# ultrasound.net
KiCad netlist of a schematic drawn in EAGLE
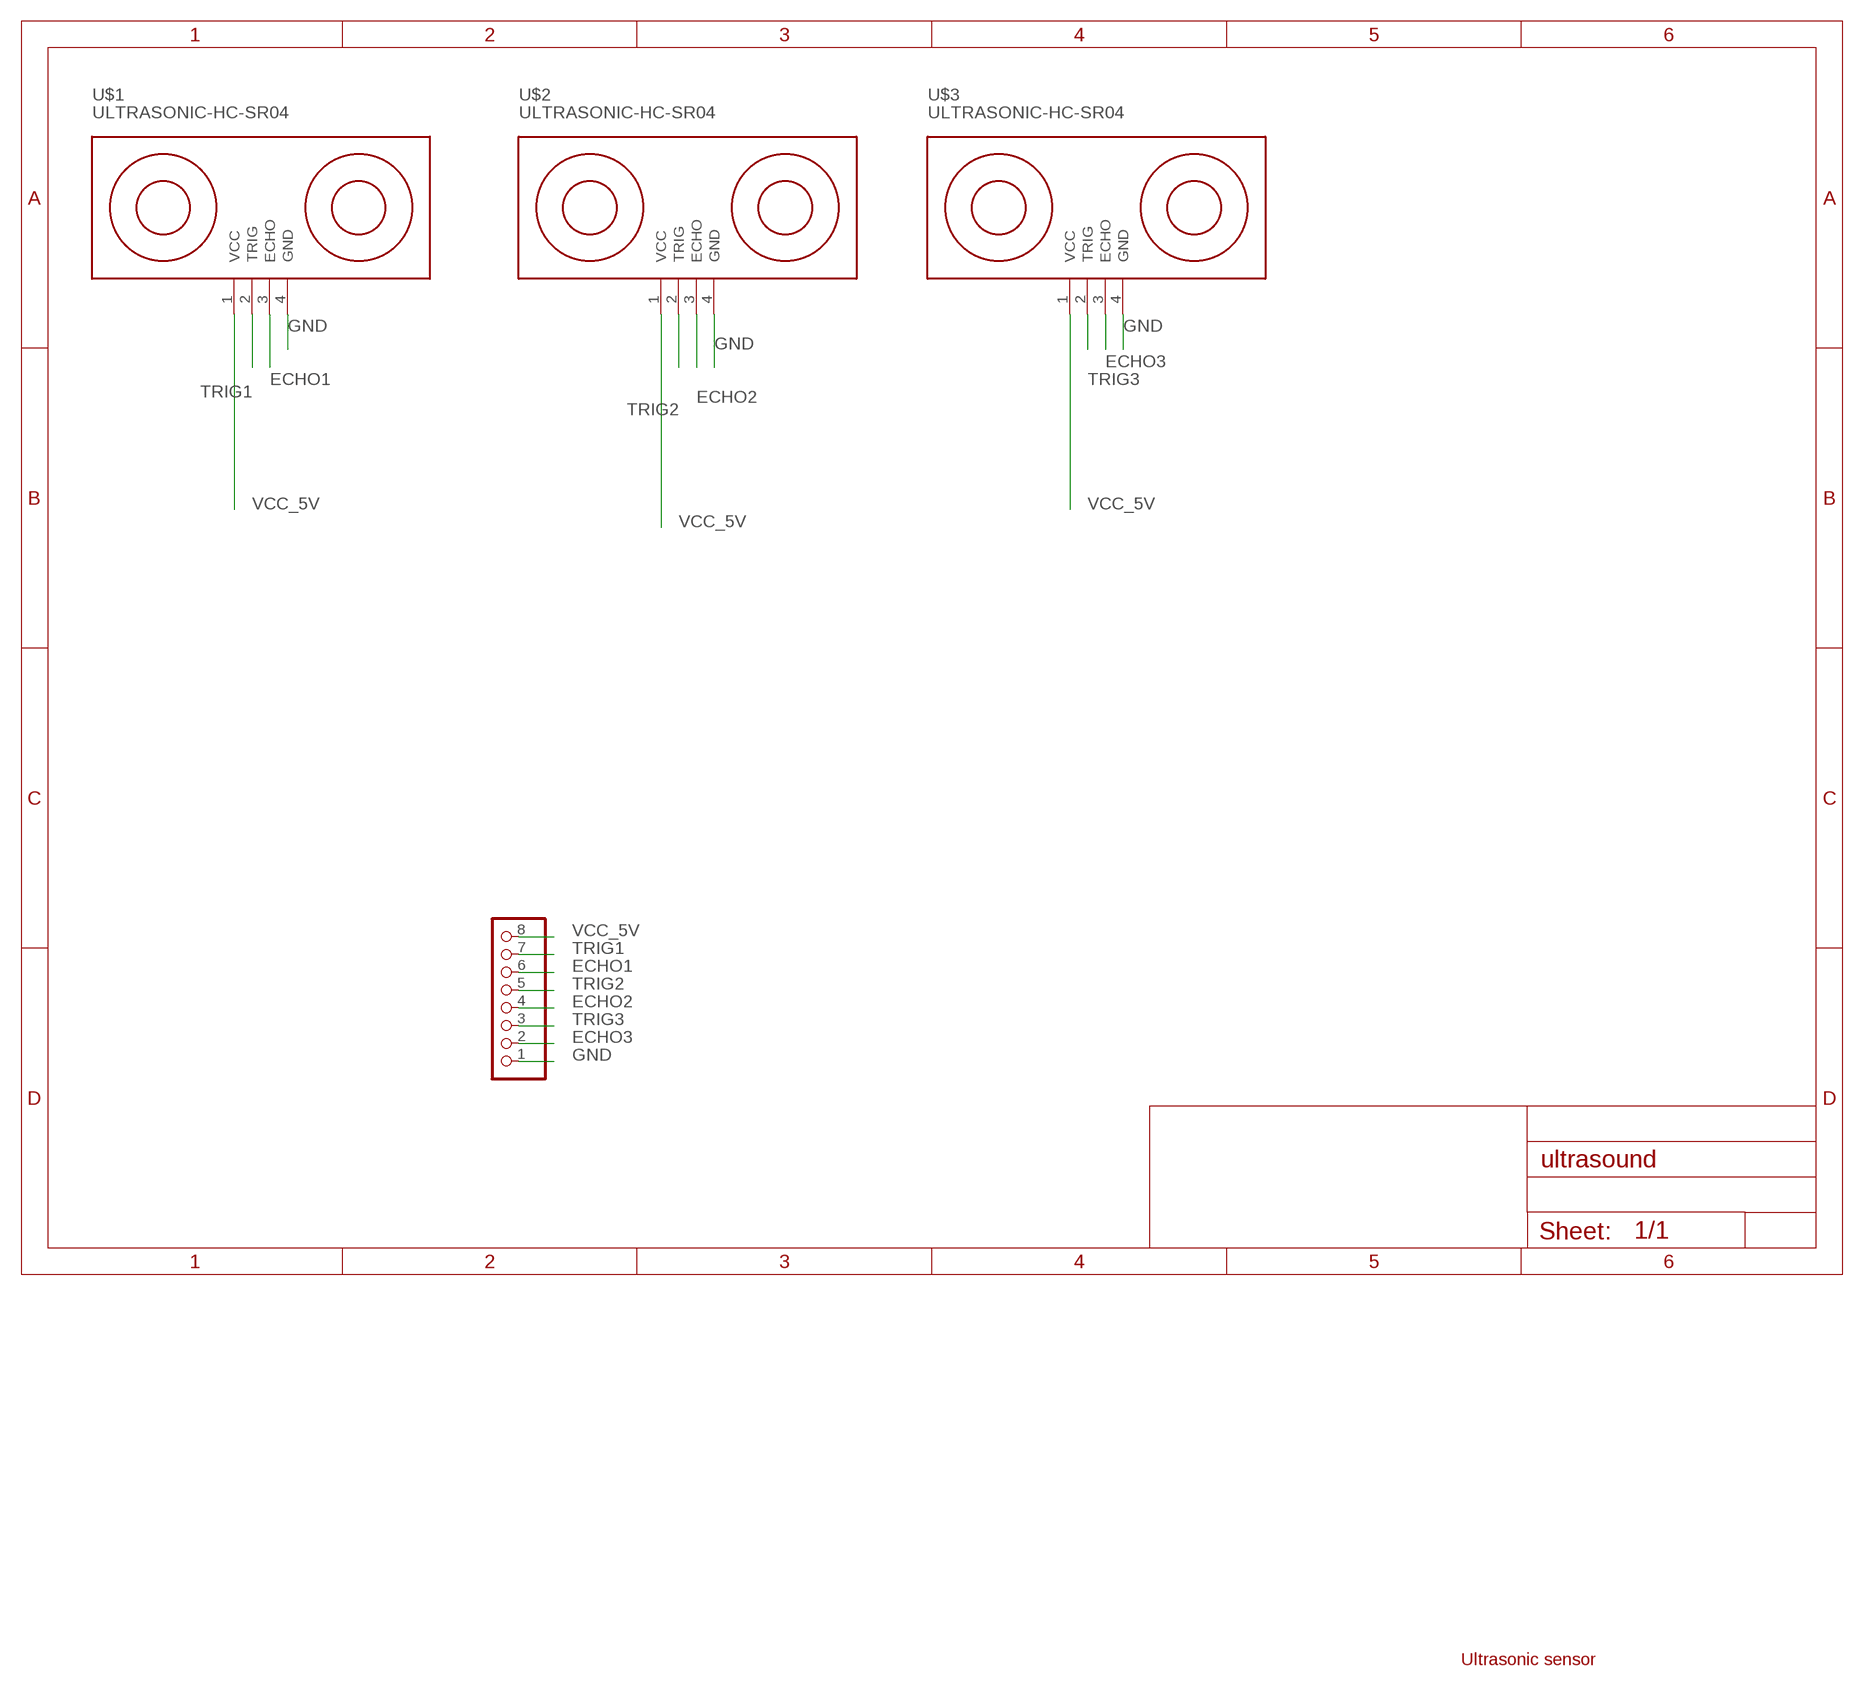
[diagram p0: schematic, sheet 1]

(export (version "E")
  (design (tool "Eeschema 10.0.6"))
  (components
    (comp (ref "JP2")
      (value "PINHD-1X8/90")
      (footprint "eagle-import:1X08_90")
      (libsource (lib "eagle-import") (part "PINHD-1X8/90"))
    )
    (comp (ref "U$1")
      (value "ULTRASONIC-HC-SR04")
      (footprint "eagle-import:ULTRASONIC-HC-SR04")
      (libsource (lib "eagle-import") (part "ULTRASONIC-HC-SR04"))
    )
    (comp (ref "U$2")
      (value "ULTRASONIC-HC-SR04")
      (footprint "eagle-import:ULTRASONIC-HC-SR04")
      (libsource (lib "eagle-import") (part "ULTRASONIC-HC-SR04"))
    )
    (comp (ref "U$3")
      (value "ULTRASONIC-HC-SR04")
      (footprint "eagle-import:ULTRASONIC-HC-SR04")
      (libsource (lib "eagle-import") (part "ULTRASONIC-HC-SR04"))
    )
  )
  (nets
    (net (code "1") (name "/ECHO1") (class "Default")
      (node (ref "JP2") (pin "6") (pinfunction "6_6") (pintype "passive"))
      (node (ref "U$1") (pin "3") (pinfunction "ECHO_3") (pintype "output"))
    )
    (net (code "2") (name "/ECHO2") (class "Default")
      (node (ref "JP2") (pin "4") (pinfunction "4_4") (pintype "passive"))
      (node (ref "U$2") (pin "3") (pinfunction "ECHO_3") (pintype "output"))
    )
    (net (code "3") (name "/ECHO3") (class "Default")
      (node (ref "JP2") (pin "2") (pinfunction "2_2") (pintype "passive"))
      (node (ref "U$3") (pin "3") (pinfunction "ECHO_3") (pintype "output"))
    )
    (net (code "4") (name "/GND") (class "Default")
      (node (ref "JP2") (pin "1") (pinfunction "1_1") (pintype "passive"))
      (node (ref "U$1") (pin "4") (pinfunction "GND_4") (pintype "power_in"))
      (node (ref "U$2") (pin "4") (pinfunction "GND_4") (pintype "power_in"))
      (node (ref "U$3") (pin "4") (pinfunction "GND_4") (pintype "power_in"))
    )
    (net (code "5") (name "/TRIG1") (class "Default")
      (node (ref "JP2") (pin "7") (pinfunction "7_7") (pintype "passive"))
      (node (ref "U$1") (pin "2") (pinfunction "TRIG_2") (pintype "input"))
    )
    (net (code "6") (name "/TRIG2") (class "Default")
      (node (ref "JP2") (pin "5") (pinfunction "5_5") (pintype "passive"))
      (node (ref "U$2") (pin "2") (pinfunction "TRIG_2") (pintype "input"))
    )
    (net (code "7") (name "/TRIG3") (class "Default")
      (node (ref "JP2") (pin "3") (pinfunction "3_3") (pintype "passive"))
      (node (ref "U$3") (pin "2") (pinfunction "TRIG_2") (pintype "input"))
    )
    (net (code "8") (name "/VCC_5V") (class "Default")
      (node (ref "JP2") (pin "8") (pinfunction "8_8") (pintype "passive"))
      (node (ref "U$1") (pin "1") (pinfunction "VCC_1") (pintype "power_in"))
      (node (ref "U$2") (pin "1") (pinfunction "VCC_1") (pintype "power_in"))
      (node (ref "U$3") (pin "1") (pinfunction "VCC_1") (pintype "power_in"))
    )
  )
)
